# SAMD21_MINIMAL.net
KiCad netlist of a schematic drawn in EAGLE
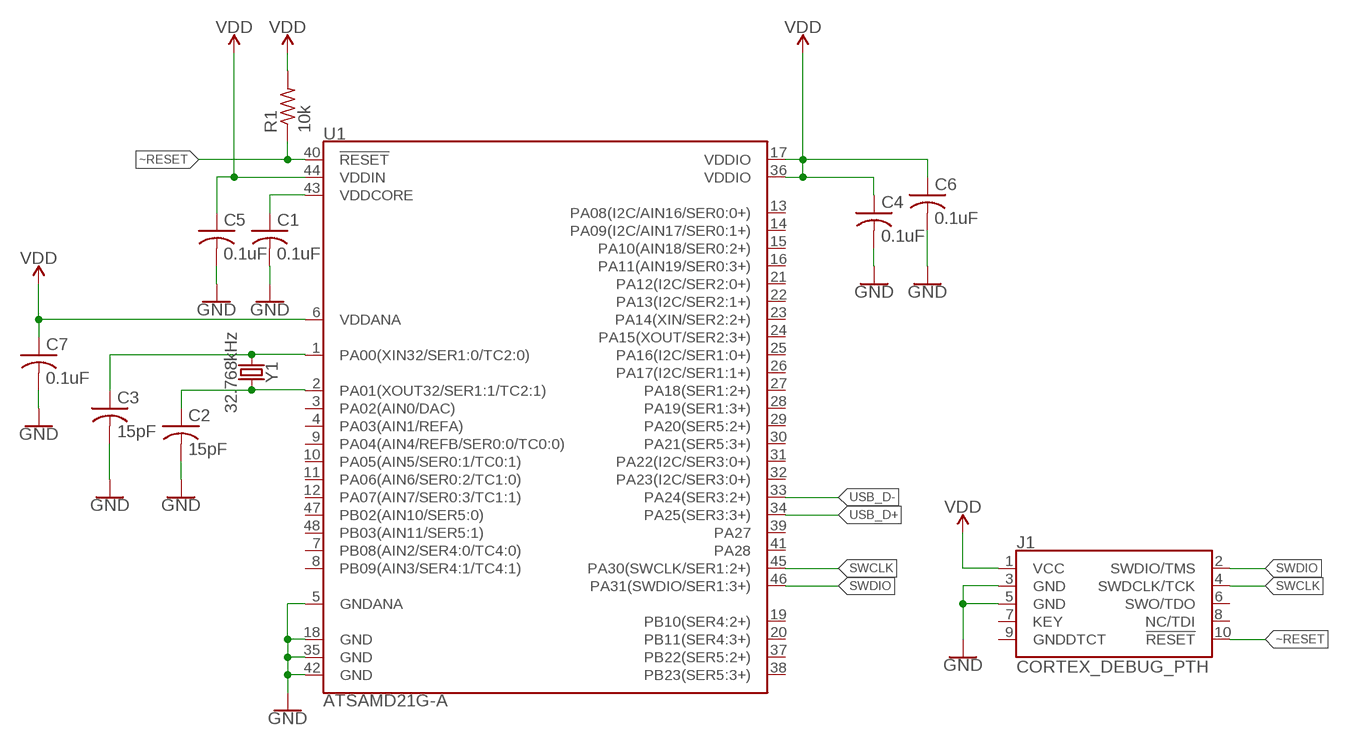
[diagram p0: schematic, sheet 1]

(export (version "E")
  (design (tool "Eeschema 10.0.6"))
  (components
    (comp (ref "C1")
      (value "0.1uF")
      (footprint "eagle-import:C0805")
      (libsource (lib "eagle-import") (part "C-USC0805"))
    )
    (comp (ref "C2")
      (value "15pF")
      (footprint "eagle-import:C0805")
      (libsource (lib "eagle-import") (part "C-USC0805"))
    )
    (comp (ref "C3")
      (value "15pF")
      (footprint "eagle-import:C0805")
      (libsource (lib "eagle-import") (part "C-USC0805"))
    )
    (comp (ref "C4")
      (value "0.1uF")
      (footprint "eagle-import:C0805")
      (libsource (lib "eagle-import") (part "C-USC0805"))
    )
    (comp (ref "C5")
      (value "0.1uF")
      (footprint "eagle-import:C0805")
      (libsource (lib "eagle-import") (part "C-USC0805"))
    )
    (comp (ref "C6")
      (value "0.1uF")
      (footprint "eagle-import:C0805")
      (libsource (lib "eagle-import") (part "C-USC0805"))
    )
    (comp (ref "C7")
      (value "0.1uF")
      (footprint "eagle-import:C0805")
      (libsource (lib "eagle-import") (part "C-USC0805"))
    )
    (comp (ref "J1")
      (value "CORTEX_DEBUG_PTH")
      (footprint "eagle-import:2X5-PTH-1.27MM")
      (libsource (lib "eagle-import") (part "CORTEX_DEBUG_PTH"))
    )
    (comp (ref "R1")
      (value "10k")
      (footprint "eagle-import:R0805")
      (libsource (lib "eagle-import") (part "R-US_R0805"))
    )
    (comp (ref "U1")
      (value "ATSAMD21G-A")
      (footprint "eagle-import:TQFP-48")
      (libsource (lib "eagle-import") (part "ATSAMD21G-A"))
    )
    (comp (ref "Y1")
      (value "32.768kHz")
      (footprint "eagle-import:CRYSTAL-SMD-MC-146")
      (libsource (lib "eagle-import") (part "CRYSTAL-32.768KHZSMD-MC146"))
    )
  )
  (nets
    (net (code "1") (name "/~{RESET}") (class "Default")
      (node (ref "J1") (pin "10") (pinfunction "~{RESET}_10") (pintype "bidirectional"))
      (node (ref "R1") (pin "1") (pinfunction "1_1") (pintype "passive"))
      (node (ref "U1") (pin "40") (pinfunction "~{RESET}_40") (pintype "bidirectional"))
    )
    (net (code "2") (name "GND") (class "Default")
      (node (ref "C1") (pin "2") (pinfunction "2_2") (pintype "passive"))
      (node (ref "C2") (pin "2") (pinfunction "2_2") (pintype "passive"))
      (node (ref "C3") (pin "2") (pinfunction "2_2") (pintype "passive"))
      (node (ref "C4") (pin "2") (pinfunction "2_2") (pintype "passive"))
      (node (ref "C5") (pin "2") (pinfunction "2_2") (pintype "passive"))
      (node (ref "C6") (pin "2") (pinfunction "2_2") (pintype "passive"))
      (node (ref "C7") (pin "2") (pinfunction "2_2") (pintype "passive"))
      (node (ref "J1") (pin "3") (pinfunction "GND_3") (pintype "bidirectional"))
      (node (ref "J1") (pin "5") (pinfunction "GND_5") (pintype "bidirectional"))
      (node (ref "U1") (pin "18") (pinfunction "GND_18") (pintype "bidirectional"))
      (node (ref "U1") (pin "35") (pinfunction "GND_35") (pintype "bidirectional"))
      (node (ref "U1") (pin "42") (pinfunction "GND_42") (pintype "bidirectional"))
      (node (ref "U1") (pin "5") (pinfunction "GNDANA_5") (pintype "bidirectional"))
    )
    (net (code "3") (name "Net-(U1-PA00(XIN32{slash}SER1:0{slash}TC2:0))") (class "Default")
      (node (ref "C3") (pin "1") (pinfunction "1_1") (pintype "passive"))
      (node (ref "U1") (pin "1") (pinfunction "PA00(XIN32/SER1:0/TC2:0)_1") (pintype "bidirectional"))
      (node (ref "Y1") (pin "P$2") (pinfunction "1_P$2") (pintype "passive"))
    )
    (net (code "4") (name "Net-(U1-PA01(XOUT32{slash}SER1:1{slash}TC2:1))") (class "Default")
      (node (ref "C2") (pin "1") (pinfunction "1_1") (pintype "passive"))
      (node (ref "U1") (pin "2") (pinfunction "PA01(XOUT32/SER1:1/TC2:1)_2") (pintype "bidirectional"))
      (node (ref "Y1") (pin "P$1") (pinfunction "2_P$1") (pintype "passive"))
    )
    (net (code "5") (name "Net-(U1-VDDCORE)") (class "Default")
      (node (ref "C1") (pin "1") (pinfunction "1_1") (pintype "passive"))
      (node (ref "U1") (pin "43") (pinfunction "VDDCORE_43") (pintype "bidirectional"))
    )
    (net (code "6") (name "SWCLK") (class "Default")
      (node (ref "J1") (pin "4") (pinfunction "SWDCLK/TCK_4") (pintype "bidirectional"))
      (node (ref "U1") (pin "45") (pinfunction "PA30(SWCLK/SER1:2+)_45") (pintype "bidirectional"))
    )
    (net (code "7") (name "SWDIO") (class "Default")
      (node (ref "J1") (pin "2") (pinfunction "SWDIO/TMS_2") (pintype "bidirectional"))
      (node (ref "U1") (pin "46") (pinfunction "PA31(SWDIO/SER1:3+)_46") (pintype "bidirectional"))
    )
    (net (code "8") (name "USB_D+") (class "Default")
      (node (ref "U1") (pin "34") (pinfunction "PA25(SER3:3+)_34") (pintype "bidirectional"))
    )
    (net (code "9") (name "USB_D-") (class "Default")
      (node (ref "U1") (pin "33") (pinfunction "PA24(SER3:2+)_33") (pintype "bidirectional"))
    )
    (net (code "10") (name "VDD") (class "Default")
      (node (ref "C4") (pin "1") (pinfunction "1_1") (pintype "passive"))
      (node (ref "C5") (pin "1") (pinfunction "1_1") (pintype "passive"))
      (node (ref "C6") (pin "1") (pinfunction "1_1") (pintype "passive"))
      (node (ref "C7") (pin "1") (pinfunction "1_1") (pintype "passive"))
      (node (ref "J1") (pin "1") (pinfunction "VCC_1") (pintype "bidirectional"))
      (node (ref "R1") (pin "2") (pinfunction "2_2") (pintype "passive"))
      (node (ref "U1") (pin "17") (pinfunction "VDDIO_17") (pintype "bidirectional"))
      (node (ref "U1") (pin "36") (pinfunction "VDDIO_36") (pintype "bidirectional"))
      (node (ref "U1") (pin "44") (pinfunction "VDDIN_44") (pintype "bidirectional"))
      (node (ref "U1") (pin "6") (pinfunction "VDDANA_6") (pintype "bidirectional"))
    )
    (net (code "11") (name "unconnected-(J1-GNDDTCT-Pad9)") (class "Default")
      (node (ref "J1") (pin "9") (pinfunction "GNDDTCT_9") (pintype "bidirectional"))
    )
    (net (code "12") (name "unconnected-(J1-KEY-Pad7)") (class "Default")
      (node (ref "J1") (pin "7") (pinfunction "KEY_7") (pintype "bidirectional"))
    )
    (net (code "13") (name "unconnected-(J1-NC{slash}TDI-Pad8)") (class "Default")
      (node (ref "J1") (pin "8") (pinfunction "NC/TDI_8") (pintype "bidirectional"))
    )
    (net (code "14") (name "unconnected-(J1-SWO{slash}TDO-Pad6)") (class "Default")
      (node (ref "J1") (pin "6") (pinfunction "SWO/TDO_6") (pintype "bidirectional"))
    )
    (net (code "15") (name "unconnected-(U1-PA02(AIN0{slash}DAC)-Pad3)") (class "Default")
      (node (ref "U1") (pin "3") (pinfunction "PA02(AIN0/DAC)_3") (pintype "bidirectional"))
    )
    (net (code "16") (name "unconnected-(U1-PA03(AIN1{slash}REFA)-Pad4)") (class "Default")
      (node (ref "U1") (pin "4") (pinfunction "PA03(AIN1/REFA)_4") (pintype "bidirectional"))
    )
    (net (code "17") (name "unconnected-(U1-PA04(AIN4{slash}REFB{slash}SER0:0{slash}TC0:0)-Pad9)") (class "Default")
      (node (ref "U1") (pin "9") (pinfunction "PA04(AIN4/REFB/SER0:0/TC0:0)_9") (pintype "bidirectional"))
    )
    (net (code "18") (name "unconnected-(U1-PA05(AIN5{slash}SER0:1{slash}TC0:1)-Pad10)") (class "Default")
      (node (ref "U1") (pin "10") (pinfunction "PA05(AIN5/SER0:1/TC0:1)_10") (pintype "bidirectional"))
    )
    (net (code "19") (name "unconnected-(U1-PA06(AIN6{slash}SER0:2{slash}TC1:0)-Pad11)") (class "Default")
      (node (ref "U1") (pin "11") (pinfunction "PA06(AIN6/SER0:2/TC1:0)_11") (pintype "bidirectional"))
    )
    (net (code "20") (name "unconnected-(U1-PA07(AIN7{slash}SER0:3{slash}TC1:1)-Pad12)") (class "Default")
      (node (ref "U1") (pin "12") (pinfunction "PA07(AIN7/SER0:3/TC1:1)_12") (pintype "bidirectional"))
    )
    (net (code "21") (name "unconnected-(U1-PA08(I2C{slash}AIN16{slash}SER0:0+)-Pad13)") (class "Default")
      (node (ref "U1") (pin "13") (pinfunction "PA08(I2C/AIN16/SER0:0+)_13") (pintype "bidirectional"))
    )
    (net (code "22") (name "unconnected-(U1-PA09(I2C{slash}AIN17{slash}SER0:1+)-Pad14)") (class "Default")
      (node (ref "U1") (pin "14") (pinfunction "PA09(I2C/AIN17/SER0:1+)_14") (pintype "bidirectional"))
    )
    (net (code "23") (name "unconnected-(U1-PA10(AIN18{slash}SER0:2+)-Pad15)") (class "Default")
      (node (ref "U1") (pin "15") (pinfunction "PA10(AIN18/SER0:2+)_15") (pintype "bidirectional"))
    )
    (net (code "24") (name "unconnected-(U1-PA11(AIN19{slash}SER0:3+)-Pad16)") (class "Default")
      (node (ref "U1") (pin "16") (pinfunction "PA11(AIN19/SER0:3+)_16") (pintype "bidirectional"))
    )
    (net (code "25") (name "unconnected-(U1-PA12(I2C{slash}SER2:0+)-Pad21)") (class "Default")
      (node (ref "U1") (pin "21") (pinfunction "PA12(I2C/SER2:0+)_21") (pintype "bidirectional"))
    )
    (net (code "26") (name "unconnected-(U1-PA13(I2C{slash}SER2:1+)-Pad22)") (class "Default")
      (node (ref "U1") (pin "22") (pinfunction "PA13(I2C/SER2:1+)_22") (pintype "bidirectional"))
    )
    (net (code "27") (name "unconnected-(U1-PA14(XIN{slash}SER2:2+)-Pad23)") (class "Default")
      (node (ref "U1") (pin "23") (pinfunction "PA14(XIN/SER2:2+)_23") (pintype "bidirectional"))
    )
    (net (code "28") (name "unconnected-(U1-PA15(XOUT{slash}SER2:3+)-Pad24)") (class "Default")
      (node (ref "U1") (pin "24") (pinfunction "PA15(XOUT/SER2:3+)_24") (pintype "bidirectional"))
    )
    (net (code "29") (name "unconnected-(U1-PA16(I2C{slash}SER1:0+)-Pad25)") (class "Default")
      (node (ref "U1") (pin "25") (pinfunction "PA16(I2C/SER1:0+)_25") (pintype "bidirectional"))
    )
    (net (code "30") (name "unconnected-(U1-PA17(I2C{slash}SER1:1+)-Pad26)") (class "Default")
      (node (ref "U1") (pin "26") (pinfunction "PA17(I2C/SER1:1+)_26") (pintype "bidirectional"))
    )
    (net (code "31") (name "unconnected-(U1-PA18(SER1:2+)-Pad27)") (class "Default")
      (node (ref "U1") (pin "27") (pinfunction "PA18(SER1:2+)_27") (pintype "bidirectional"))
    )
    (net (code "32") (name "unconnected-(U1-PA19(SER1:3+)-Pad28)") (class "Default")
      (node (ref "U1") (pin "28") (pinfunction "PA19(SER1:3+)_28") (pintype "bidirectional"))
    )
    (net (code "33") (name "unconnected-(U1-PA20(SER5:2+)-Pad29)") (class "Default")
      (node (ref "U1") (pin "29") (pinfunction "PA20(SER5:2+)_29") (pintype "bidirectional"))
    )
    (net (code "34") (name "unconnected-(U1-PA21(SER5:3+)-Pad30)") (class "Default")
      (node (ref "U1") (pin "30") (pinfunction "PA21(SER5:3+)_30") (pintype "bidirectional"))
    )
    (net (code "35") (name "unconnected-(U1-PA22(I2C{slash}SER3:0+)-Pad31)") (class "Default")
      (node (ref "U1") (pin "31") (pinfunction "PA22(I2C/SER3:0+)_31") (pintype "bidirectional"))
    )
    (net (code "36") (name "unconnected-(U1-PA23(I2C{slash}SER3:0+)-Pad32)") (class "Default")
      (node (ref "U1") (pin "32") (pinfunction "PA23(I2C/SER3:0+)_32") (pintype "bidirectional"))
    )
    (net (code "37") (name "unconnected-(U1-PA27-Pad39)") (class "Default")
      (node (ref "U1") (pin "39") (pinfunction "PA27_39") (pintype "bidirectional"))
    )
    (net (code "38") (name "unconnected-(U1-PA28-Pad41)") (class "Default")
      (node (ref "U1") (pin "41") (pinfunction "PA28_41") (pintype "bidirectional"))
    )
    (net (code "39") (name "unconnected-(U1-PB02(AIN10{slash}SER5:0)-Pad47)") (class "Default")
      (node (ref "U1") (pin "47") (pinfunction "PB02(AIN10/SER5:0)_47") (pintype "bidirectional"))
    )
    (net (code "40") (name "unconnected-(U1-PB03(AIN11{slash}SER5:1)-Pad48)") (class "Default")
      (node (ref "U1") (pin "48") (pinfunction "PB03(AIN11/SER5:1)_48") (pintype "bidirectional"))
    )
    (net (code "41") (name "unconnected-(U1-PB08(AIN2{slash}SER4:0{slash}TC4:0)-Pad7)") (class "Default")
      (node (ref "U1") (pin "7") (pinfunction "PB08(AIN2/SER4:0/TC4:0)_7") (pintype "bidirectional"))
    )
    (net (code "42") (name "unconnected-(U1-PB09(AIN3{slash}SER4:1{slash}TC4:1)-Pad8)") (class "Default")
      (node (ref "U1") (pin "8") (pinfunction "PB09(AIN3/SER4:1/TC4:1)_8") (pintype "bidirectional"))
    )
    (net (code "43") (name "unconnected-(U1-PB10(SER4:2+)-Pad19)") (class "Default")
      (node (ref "U1") (pin "19") (pinfunction "PB10(SER4:2+)_19") (pintype "bidirectional"))
    )
    (net (code "44") (name "unconnected-(U1-PB11(SER4:3+)-Pad20)") (class "Default")
      (node (ref "U1") (pin "20") (pinfunction "PB11(SER4:3+)_20") (pintype "bidirectional"))
    )
    (net (code "45") (name "unconnected-(U1-PB22(SER5:2+)-Pad37)") (class "Default")
      (node (ref "U1") (pin "37") (pinfunction "PB22(SER5:2+)_37") (pintype "bidirectional"))
    )
    (net (code "46") (name "unconnected-(U1-PB23(SER5:3+)-Pad38)") (class "Default")
      (node (ref "U1") (pin "38") (pinfunction "PB23(SER5:3+)_38") (pintype "bidirectional"))
    )
  )
)
